# 10_12-Bit_RasPi-ADC_HAT_v21.net
KiCad netlist of a schematic drawn in EAGLE
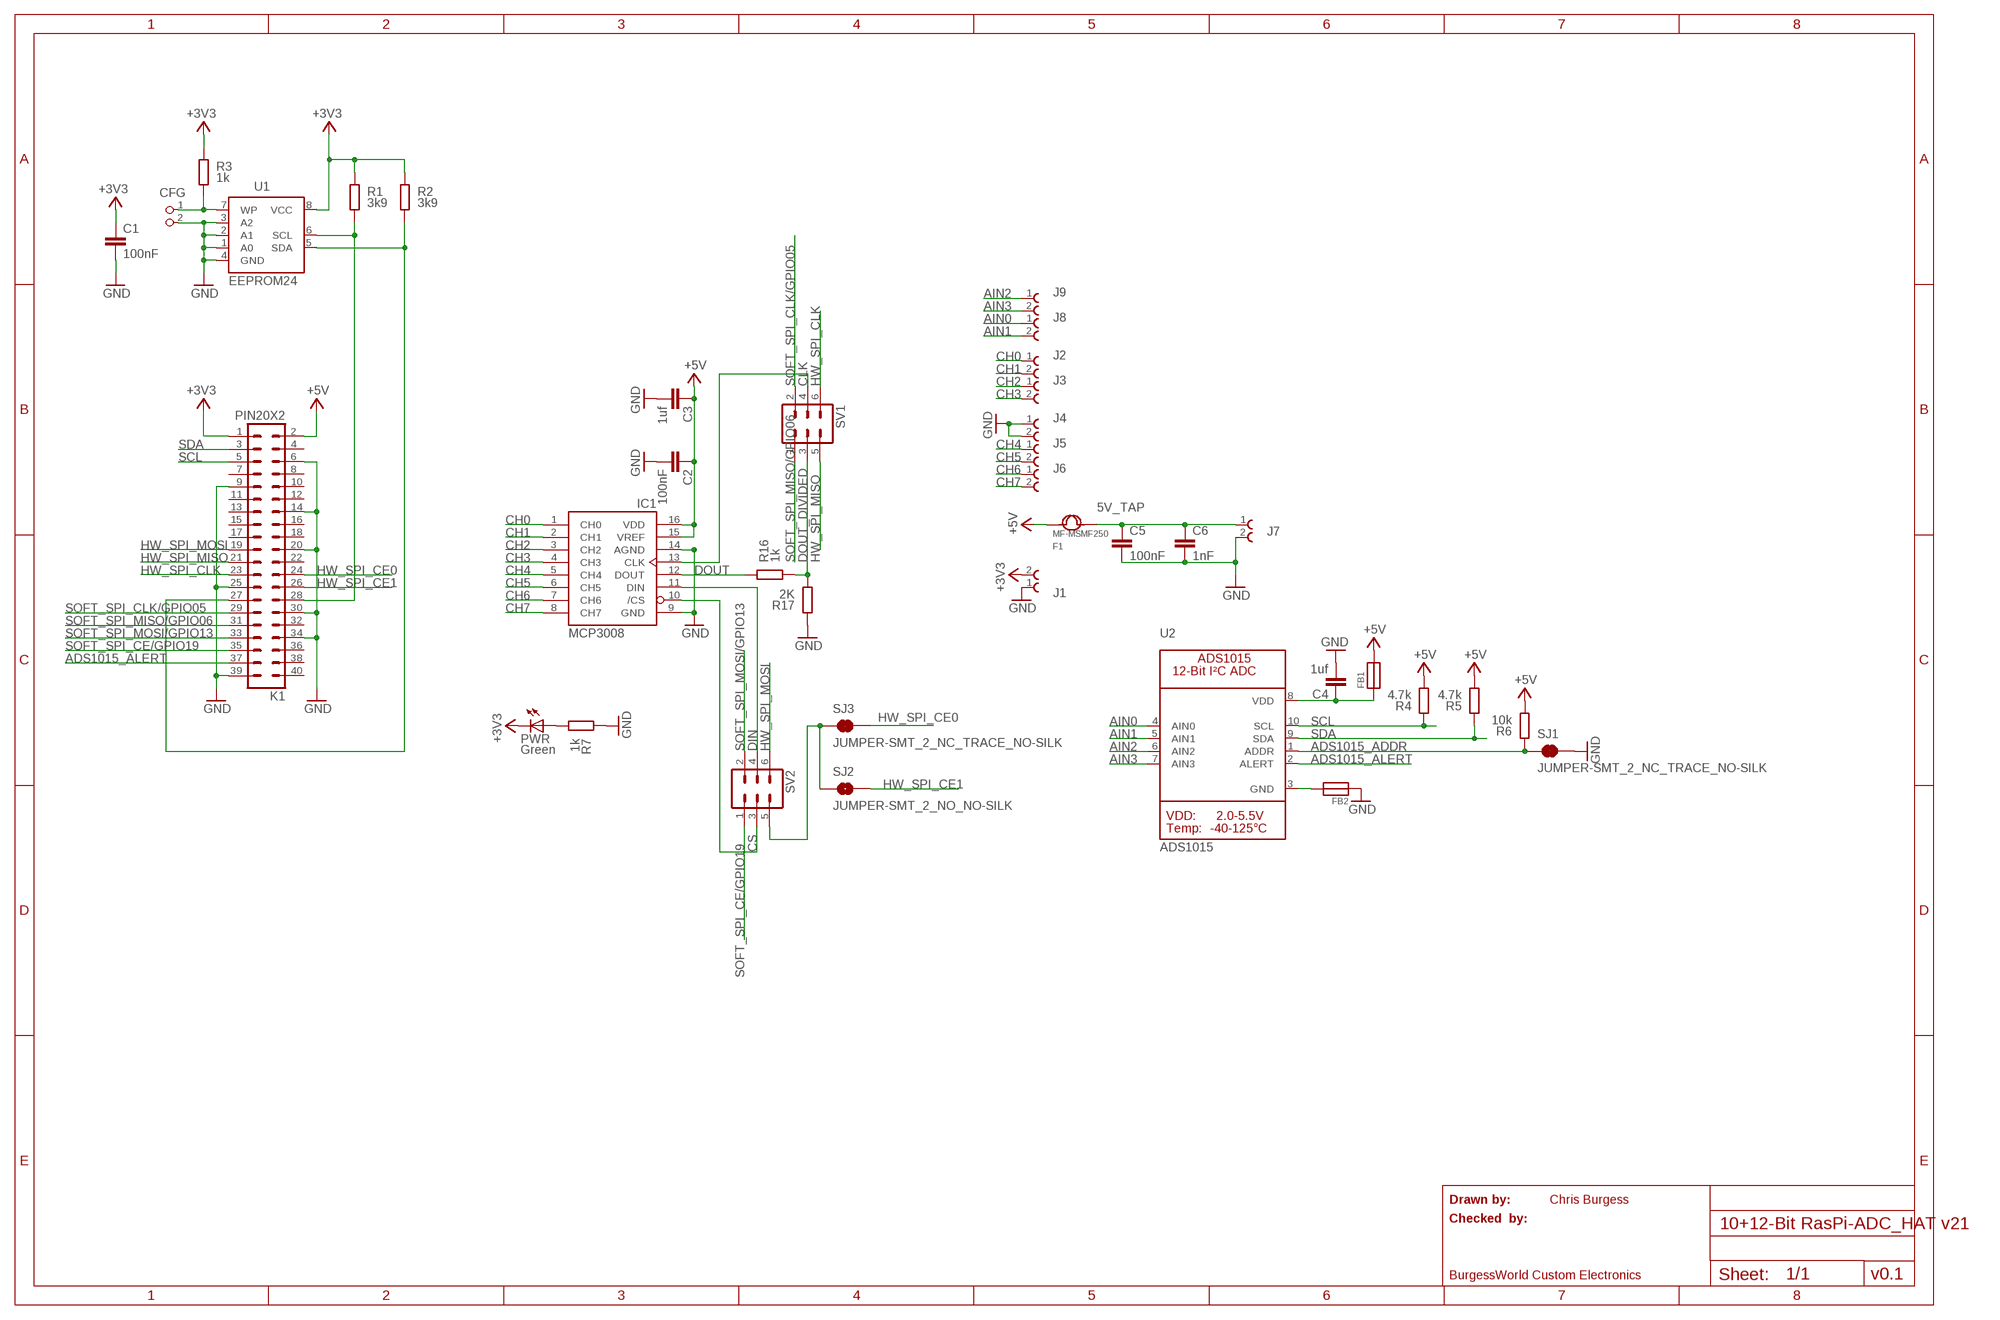
[diagram p0: schematic, sheet 1]

(export (version "E")
  (design (tool "Eeschema 10.0.6"))
  (components
    (comp (ref "C1")
      (value "100nF")
      (footprint "eagle-import:C0805K")
      (libsource (lib "eagle-import") (part "C-EUC0805K"))
    )
    (comp (ref "C2")
      (value "100nF")
      (footprint "eagle-import:C0805K")
      (libsource (lib "eagle-import") (part "C-EUC0805K"))
    )
    (comp (ref "C3")
      (value "1uf")
      (footprint "eagle-import:C0805K")
      (libsource (lib "eagle-import") (part "C-EUC0805K"))
    )
    (comp (ref "C4")
      (value "1uf")
      (footprint "eagle-import:C0805K")
      (libsource (lib "eagle-import") (part "C-EUC0805K"))
    )
    (comp (ref "C5")
      (value "100nF")
      (footprint "eagle-import:C0805K")
      (libsource (lib "eagle-import") (part "C-EUC0805K"))
    )
    (comp (ref "C6")
      (value "1nF")
      (footprint "eagle-import:C0805K")
      (libsource (lib "eagle-import") (part "C-EUC0805K"))
    )
    (comp (ref "CFG")
      (value "PIN2_100")
      (footprint "eagle-import:PIN_W_2")
      (libsource (lib "eagle-import") (part "PIN2_100"))
    )
    (comp (ref "F1")
      (value "MF-MSMF250")
      (footprint "eagle-import:F1812")
      (fields (field (name "MPN") "MF-MSMF050-2"))
      (libsource (lib "eagle-import") (part "SMD-PPTC-USE-PPTC-0.50A-15V-0.15OHM(1812)"))
    )
    (comp (ref "FB1")
      (value "FERRITE0805")
      (footprint "eagle-import:0805")
      (libsource (lib "eagle-import") (part "FERRITE0805"))
    )
    (comp (ref "FB2")
      (value "FERRITE0805")
      (footprint "eagle-import:0805")
      (libsource (lib "eagle-import") (part "FERRITE0805"))
    )
    (comp (ref "IC1")
      (value "MCP3008")
      (footprint "eagle-import:DIL16")
      (libsource (lib "eagle-import") (part "MCP3008"))
    )
    (comp (ref "J1")
      (value "691214110002")
      (footprint "eagle-import:691214110002")
      (libsource (lib "eagle-import") (part "691214110002"))
    )
    (comp (ref "J2")
      (value "691214110002")
      (footprint "eagle-import:691214110002")
      (libsource (lib "eagle-import") (part "691214110002"))
    )
    (comp (ref "J3")
      (value "691214110002")
      (footprint "eagle-import:691214110002")
      (libsource (lib "eagle-import") (part "691214110002"))
    )
    (comp (ref "J4")
      (value "691214110002")
      (footprint "eagle-import:691214110002")
      (libsource (lib "eagle-import") (part "691214110002"))
    )
    (comp (ref "J5")
      (value "691214110002")
      (footprint "eagle-import:691214110002")
      (libsource (lib "eagle-import") (part "691214110002"))
    )
    (comp (ref "J6")
      (value "691214110002")
      (footprint "eagle-import:691214110002")
      (libsource (lib "eagle-import") (part "691214110002"))
    )
    (comp (ref "J7")
      (value "691214110002")
      (footprint "eagle-import:691214110002")
      (libsource (lib "eagle-import") (part "691214110002"))
    )
    (comp (ref "J8")
      (value "691214110002")
      (footprint "eagle-import:691214110002")
      (libsource (lib "eagle-import") (part "691214110002"))
    )
    (comp (ref "J9")
      (value "691214110002")
      (footprint "eagle-import:691214110002")
      (libsource (lib "eagle-import") (part "691214110002"))
    )
    (comp (ref "K1")
      (value "PIN20X2")
      (footprint "eagle-import:PIN_20X2")
      (libsource (lib "eagle-import") (part "PIN20X2"))
    )
    (comp (ref "PWR")
      (value "Green")
      (footprint "eagle-import:CHIPLED_0805")
      (libsource (lib "eagle-import") (part "LEDCHIPLED_0805"))
    )
    (comp (ref "R1")
      (value "3k9")
      (footprint "eagle-import:M0805")
      (fields (field (name "TOLERANCE") "5%"))
      (libsource (lib "eagle-import") (part "R-EU_M0805"))
    )
    (comp (ref "R2")
      (value "3k9")
      (footprint "eagle-import:M0805")
      (fields (field (name "TOLERANCE") "5%"))
      (libsource (lib "eagle-import") (part "R-EU_M0805"))
    )
    (comp (ref "R3")
      (value "1k")
      (footprint "eagle-import:M0805")
      (fields (field (name "TOLERANCE") "5%"))
      (libsource (lib "eagle-import") (part "R-EU_M0805"))
    )
    (comp (ref "R4")
      (value "4.7k")
      (footprint "eagle-import:M0805")
      (fields (field (name "TOLERANCE") "5%"))
      (libsource (lib "eagle-import") (part "R-EU_M0805"))
    )
    (comp (ref "R5")
      (value "4.7k")
      (footprint "eagle-import:M0805")
      (fields (field (name "TOLERANCE") "5%"))
      (libsource (lib "eagle-import") (part "R-EU_M0805"))
    )
    (comp (ref "R6")
      (value "10k")
      (footprint "eagle-import:M0805")
      (fields (field (name "TOLERANCE") "5%"))
      (libsource (lib "eagle-import") (part "R-EU_M0805"))
    )
    (comp (ref "R7")
      (value "1k")
      (footprint "eagle-import:M0805")
      (fields (field (name "TOLERANCE") "5%"))
      (libsource (lib "eagle-import") (part "R-EU_M0805"))
    )
    (comp (ref "R16")
      (value "1k")
      (footprint "eagle-import:M0805")
      (fields (field (name "TOLERANCE") "5%"))
      (libsource (lib "eagle-import") (part "R-EU_M0805"))
    )
    (comp (ref "R17")
      (value "2K")
      (footprint "eagle-import:M0805")
      (fields (field (name "TOLERANCE") "5%"))
      (libsource (lib "eagle-import") (part "R-EU_M0805"))
    )
    (comp (ref "SJ1")
      (value "JUMPER-SMT_2_NC_TRACE_NO-SILK")
      (footprint "eagle-import:SMT-JUMPER_2_NC_TRACE_NO-SILK")
      (libsource (lib "eagle-import") (part "JUMPER-SMT_2_NC_TRACE_NO-SILK"))
    )
    (comp (ref "SJ2")
      (value "JUMPER-SMT_2_NO_NO-SILK")
      (footprint "eagle-import:SMT-JUMPER_2_NO_NO-SILK")
      (libsource (lib "eagle-import") (part "JUMPER-SMT_2_NO_NO-SILK"))
    )
    (comp (ref "SJ3")
      (value "JUMPER-SMT_2_NC_TRACE_NO-SILK")
      (footprint "eagle-import:SMT-JUMPER_2_NC_TRACE_NO-SILK")
      (libsource (lib "eagle-import") (part "JUMPER-SMT_2_NC_TRACE_NO-SILK"))
    )
    (comp (ref "SV1")
      (value "MA03-2")
      (footprint "eagle-import:MA03-2")
      (libsource (lib "eagle-import") (part "MA03-2"))
    )
    (comp (ref "SV2")
      (value "MA03-2")
      (footprint "eagle-import:MA03-2")
      (libsource (lib "eagle-import") (part "MA03-2"))
    )
    (comp (ref "U1")
      (value "EEPROM24")
      (footprint "eagle-import:SOIC8")
      (libsource (lib "eagle-import") (part "EEPROM24"))
    )
    (comp (ref "U2")
      (value "ADS1015")
      (footprint "eagle-import:MSOP10")
      (libsource (lib "eagle-import") (part "ADC_ADS1015"))
    )
  )
  (nets
    (net (code "1") (name "+3V3") (class "Default")
      (node (ref "C1") (pin "1") (pinfunction "1_1") (pintype "passive"))
      (node (ref "J1") (pin "2") (pinfunction "2_2") (pintype "passive"))
      (node (ref "K1") (pin "1") (pinfunction "1_1") (pintype "passive"))
      (node (ref "PWR") (pin "C") (pinfunction "C_C") (pintype "passive"))
      (node (ref "R1") (pin "2") (pinfunction "2_2") (pintype "passive"))
      (node (ref "R2") (pin "2") (pinfunction "2_2") (pintype "passive"))
      (node (ref "R3") (pin "2") (pinfunction "2_2") (pintype "passive"))
      (node (ref "U1") (pin "8") (pinfunction "VCC_8") (pintype "power_in"))
    )
    (net (code "2") (name "+5V") (class "Default")
      (node (ref "C2") (pin "1") (pinfunction "1_1") (pintype "passive"))
      (node (ref "C3") (pin "1") (pinfunction "1_1") (pintype "passive"))
      (node (ref "F1") (pin "1") (pinfunction "1_1") (pintype "bidirectional"))
      (node (ref "FB1") (pin "2") (pinfunction "P$2_2") (pintype "bidirectional"))
      (node (ref "IC1") (pin "15") (pinfunction "VREF_15") (pintype "input"))
      (node (ref "IC1") (pin "16") (pinfunction "VDD_16") (pintype "power_in"))
      (node (ref "K1") (pin "2") (pinfunction "2_2") (pintype "passive"))
      (node (ref "R4") (pin "1") (pinfunction "1_1") (pintype "passive"))
      (node (ref "R5") (pin "1") (pinfunction "1_1") (pintype "passive"))
      (node (ref "R6") (pin "1") (pinfunction "1_1") (pintype "passive"))
    )
    (net (code "3") (name "/5V_TAP") (class "Default")
      (node (ref "C5") (pin "1") (pinfunction "1_1") (pintype "passive"))
      (node (ref "C6") (pin "1") (pinfunction "1_1") (pintype "passive"))
      (node (ref "F1") (pin "2") (pinfunction "2_2") (pintype "bidirectional"))
      (node (ref "J7") (pin "1") (pinfunction "1_1") (pintype "passive"))
    )
    (net (code "4") (name "/ADS1015_ADDR") (class "Default")
      (node (ref "R6") (pin "2") (pinfunction "2_2") (pintype "passive"))
      (node (ref "SJ1") (pin "1") (pinfunction "1_1") (pintype "passive"))
      (node (ref "U2") (pin "1") (pinfunction "ADDR_1") (pintype "bidirectional"))
    )
    (net (code "5") (name "/ADS1015_ALERT") (class "Default")
      (node (ref "K1") (pin "37") (pinfunction "37_37") (pintype "passive"))
      (node (ref "U2") (pin "2") (pinfunction "ALERT_2") (pintype "bidirectional"))
    )
    (net (code "6") (name "/AIN0") (class "Default")
      (node (ref "J8") (pin "1") (pinfunction "1_1") (pintype "passive"))
      (node (ref "U2") (pin "4") (pinfunction "AIN0_4") (pintype "bidirectional"))
    )
    (net (code "7") (name "/AIN1") (class "Default")
      (node (ref "J8") (pin "2") (pinfunction "2_2") (pintype "passive"))
      (node (ref "U2") (pin "5") (pinfunction "AIN1_5") (pintype "bidirectional"))
    )
    (net (code "8") (name "/AIN2") (class "Default")
      (node (ref "J9") (pin "1") (pinfunction "1_1") (pintype "passive"))
      (node (ref "U2") (pin "6") (pinfunction "AIN2_6") (pintype "bidirectional"))
    )
    (net (code "9") (name "/AIN3") (class "Default")
      (node (ref "J9") (pin "2") (pinfunction "2_2") (pintype "passive"))
      (node (ref "U2") (pin "7") (pinfunction "AIN3_7") (pintype "bidirectional"))
    )
    (net (code "10") (name "/CH0") (class "Default")
      (node (ref "IC1") (pin "1") (pinfunction "CH0_1") (pintype "input"))
      (node (ref "J2") (pin "1") (pinfunction "1_1") (pintype "passive"))
    )
    (net (code "11") (name "/CH1") (class "Default")
      (node (ref "IC1") (pin "2") (pinfunction "CH1_2") (pintype "input"))
      (node (ref "J2") (pin "2") (pinfunction "2_2") (pintype "passive"))
    )
    (net (code "12") (name "/CH2") (class "Default")
      (node (ref "IC1") (pin "3") (pinfunction "CH2_3") (pintype "input"))
      (node (ref "J3") (pin "1") (pinfunction "1_1") (pintype "passive"))
    )
    (net (code "13") (name "/CH3") (class "Default")
      (node (ref "IC1") (pin "4") (pinfunction "CH3_4") (pintype "input"))
      (node (ref "J3") (pin "2") (pinfunction "2_2") (pintype "passive"))
    )
    (net (code "14") (name "/CH4") (class "Default")
      (node (ref "IC1") (pin "5") (pinfunction "CH4_5") (pintype "input"))
      (node (ref "J5") (pin "1") (pinfunction "1_1") (pintype "passive"))
    )
    (net (code "15") (name "/CH5") (class "Default")
      (node (ref "IC1") (pin "6") (pinfunction "CH5_6") (pintype "input"))
      (node (ref "J5") (pin "2") (pinfunction "2_2") (pintype "passive"))
    )
    (net (code "16") (name "/CH6") (class "Default")
      (node (ref "IC1") (pin "7") (pinfunction "CH6_7") (pintype "input"))
      (node (ref "J6") (pin "1") (pinfunction "1_1") (pintype "passive"))
    )
    (net (code "17") (name "/CH7") (class "Default")
      (node (ref "IC1") (pin "8") (pinfunction "CH7_8") (pintype "input"))
      (node (ref "J6") (pin "2") (pinfunction "2_2") (pintype "passive"))
    )
    (net (code "18") (name "/CLK") (class "Default")
      (node (ref "IC1") (pin "13") (pinfunction "CLK_13") (pintype "input"))
      (node (ref "SV1") (pin "4") (pinfunction "4_4") (pintype "passive"))
    )
    (net (code "19") (name "/CS") (class "Default")
      (node (ref "IC1") (pin "10") (pinfunction "/CS_10") (pintype "input"))
      (node (ref "SV2") (pin "3") (pinfunction "3_3") (pintype "passive"))
    )
    (net (code "20") (name "/DIN") (class "Default")
      (node (ref "IC1") (pin "11") (pinfunction "DIN_11") (pintype "input"))
      (node (ref "SV2") (pin "4") (pinfunction "4_4") (pintype "passive"))
    )
    (net (code "21") (name "/DOUT") (class "Default")
      (node (ref "IC1") (pin "12") (pinfunction "DOUT_12") (pintype "output"))
      (node (ref "R16") (pin "2") (pinfunction "2_2") (pintype "passive"))
    )
    (net (code "22") (name "/DOUT_DIVIDED") (class "Default")
      (node (ref "R16") (pin "1") (pinfunction "1_1") (pintype "passive"))
      (node (ref "R17") (pin "1") (pinfunction "1_1") (pintype "passive"))
      (node (ref "SV1") (pin "3") (pinfunction "3_3") (pintype "passive"))
    )
    (net (code "23") (name "/HW_SPI_CE0") (class "Default")
      (node (ref "K1") (pin "24") (pinfunction "24_24") (pintype "passive"))
      (node (ref "SJ3") (pin "2") (pinfunction "2_2") (pintype "passive"))
    )
    (net (code "24") (name "/HW_SPI_CE1") (class "Default")
      (node (ref "K1") (pin "26") (pinfunction "26_26") (pintype "passive"))
      (node (ref "SJ2") (pin "2") (pinfunction "2_2") (pintype "passive"))
    )
    (net (code "25") (name "/HW_SPI_CLK") (class "Default")
      (node (ref "K1") (pin "23") (pinfunction "23_23") (pintype "passive"))
      (node (ref "SV1") (pin "6") (pinfunction "6_6") (pintype "passive"))
    )
    (net (code "26") (name "/HW_SPI_MISO") (class "Default")
      (node (ref "K1") (pin "21") (pinfunction "21_21") (pintype "passive"))
      (node (ref "SV1") (pin "5") (pinfunction "5_5") (pintype "passive"))
    )
    (net (code "27") (name "/HW_SPI_MOSI") (class "Default")
      (node (ref "K1") (pin "19") (pinfunction "19_19") (pintype "passive"))
      (node (ref "SV2") (pin "6") (pinfunction "6_6") (pintype "passive"))
    )
    (net (code "28") (name "/SCL") (class "Default")
      (node (ref "K1") (pin "5") (pinfunction "5_5") (pintype "passive"))
      (node (ref "R4") (pin "2") (pinfunction "2_2") (pintype "passive"))
      (node (ref "U2") (pin "10") (pinfunction "SCL_10") (pintype "bidirectional"))
    )
    (net (code "29") (name "/SDA") (class "Default")
      (node (ref "K1") (pin "3") (pinfunction "3_3") (pintype "passive"))
      (node (ref "R5") (pin "2") (pinfunction "2_2") (pintype "passive"))
      (node (ref "U2") (pin "9") (pinfunction "SDA_9") (pintype "bidirectional"))
    )
    (net (code "30") (name "/SOFT_SPI_CE{slash}GPIO19") (class "Default")
      (node (ref "K1") (pin "35") (pinfunction "35_35") (pintype "passive"))
      (node (ref "SV2") (pin "1") (pinfunction "1_1") (pintype "passive"))
    )
    (net (code "31") (name "/SOFT_SPI_CLK{slash}GPIO05") (class "Default")
      (node (ref "K1") (pin "29") (pinfunction "29_29") (pintype "passive"))
      (node (ref "SV1") (pin "2") (pinfunction "2_2") (pintype "passive"))
    )
    (net (code "32") (name "/SOFT_SPI_MISO{slash}GPIO06") (class "Default")
      (node (ref "K1") (pin "31") (pinfunction "31_31") (pintype "passive"))
      (node (ref "SV1") (pin "1") (pinfunction "1_1") (pintype "passive"))
    )
    (net (code "33") (name "/SOFT_SPI_MOSI{slash}GPIO13") (class "Default")
      (node (ref "K1") (pin "33") (pinfunction "33_33") (pintype "passive"))
      (node (ref "SV2") (pin "2") (pinfunction "2_2") (pintype "passive"))
    )
    (net (code "34") (name "GND") (class "Default")
      (node (ref "C1") (pin "2") (pinfunction "2_2") (pintype "passive"))
      (node (ref "C2") (pin "2") (pinfunction "2_2") (pintype "passive"))
      (node (ref "C3") (pin "2") (pinfunction "2_2") (pintype "passive"))
      (node (ref "C4") (pin "2") (pinfunction "2_2") (pintype "passive"))
      (node (ref "C5") (pin "2") (pinfunction "2_2") (pintype "passive"))
      (node (ref "C6") (pin "2") (pinfunction "2_2") (pintype "passive"))
      (node (ref "CFG") (pin "2") (pinfunction "2_2") (pintype "passive"))
      (node (ref "FB2") (pin "1") (pinfunction "P$1_1") (pintype "bidirectional"))
      (node (ref "IC1") (pin "14") (pinfunction "AGND_14") (pintype "power_in"))
      (node (ref "IC1") (pin "9") (pinfunction "GND_9") (pintype "power_in"))
      (node (ref "J1") (pin "1") (pinfunction "1_1") (pintype "passive"))
      (node (ref "J4") (pin "1") (pinfunction "1_1") (pintype "passive"))
      (node (ref "J4") (pin "2") (pinfunction "2_2") (pintype "passive"))
      (node (ref "J7") (pin "2") (pinfunction "2_2") (pintype "passive"))
      (node (ref "K1") (pin "14") (pinfunction "14_14") (pintype "passive"))
      (node (ref "K1") (pin "20") (pinfunction "20_20") (pintype "passive"))
      (node (ref "K1") (pin "25") (pinfunction "25_25") (pintype "passive"))
      (node (ref "K1") (pin "30") (pinfunction "30_30") (pintype "passive"))
      (node (ref "K1") (pin "34") (pinfunction "34_34") (pintype "passive"))
      (node (ref "K1") (pin "39") (pinfunction "39_39") (pintype "passive"))
      (node (ref "K1") (pin "6") (pinfunction "6_6") (pintype "passive"))
      (node (ref "K1") (pin "9") (pinfunction "9_9") (pintype "passive"))
      (node (ref "R17") (pin "2") (pinfunction "2_2") (pintype "passive"))
      (node (ref "R7") (pin "2") (pinfunction "2_2") (pintype "passive"))
      (node (ref "SJ1") (pin "2") (pinfunction "2_2") (pintype "passive"))
      (node (ref "U1") (pin "1") (pinfunction "A0_1") (pintype "input"))
      (node (ref "U1") (pin "2") (pinfunction "A1_2") (pintype "input"))
      (node (ref "U1") (pin "3") (pinfunction "A2_3") (pintype "input"))
      (node (ref "U1") (pin "4") (pinfunction "GND_4") (pintype "power_in"))
    )
    (net (code "35") (name "Net-(FB1-P$1)") (class "Default")
      (node (ref "C4") (pin "1") (pinfunction "1_1") (pintype "passive"))
      (node (ref "FB1") (pin "1") (pinfunction "P$1_1") (pintype "bidirectional"))
      (node (ref "U2") (pin "8") (pinfunction "VDD_8") (pintype "bidirectional"))
    )
    (net (code "36") (name "Net-(FB2-P$2)") (class "Default")
      (node (ref "FB2") (pin "2") (pinfunction "P$2_2") (pintype "bidirectional"))
      (node (ref "U2") (pin "3") (pinfunction "GND_3") (pintype "bidirectional"))
    )
    (net (code "37") (name "Net-(PWR-PadA)") (class "Default")
      (node (ref "PWR") (pin "A") (pinfunction "A_A") (pintype "passive"))
      (node (ref "R7") (pin "1") (pinfunction "1_1") (pintype "passive"))
    )
    (net (code "38") (name "Net-(SJ2-Pad1)") (class "Default")
      (node (ref "SJ2") (pin "1") (pinfunction "1_1") (pintype "passive"))
      (node (ref "SJ3") (pin "1") (pinfunction "1_1") (pintype "passive"))
      (node (ref "SV2") (pin "5") (pinfunction "5_5") (pintype "passive"))
    )
    (net (code "39") (name "Net-(U1-SCL)") (class "Default")
      (node (ref "K1") (pin "28") (pinfunction "28_28") (pintype "passive"))
      (node (ref "R1") (pin "1") (pinfunction "1_1") (pintype "passive"))
      (node (ref "U1") (pin "6") (pinfunction "SCL_6") (pintype "input"))
    )
    (net (code "40") (name "Net-(U1-SDA)") (class "Default")
      (node (ref "K1") (pin "27") (pinfunction "27_27") (pintype "passive"))
      (node (ref "R2") (pin "1") (pinfunction "1_1") (pintype "passive"))
      (node (ref "U1") (pin "5") (pinfunction "SDA_5") (pintype "bidirectional"))
    )
    (net (code "41") (name "Net-(U1-WP)") (class "Default")
      (node (ref "CFG") (pin "1") (pinfunction "1_1") (pintype "passive"))
      (node (ref "R3") (pin "1") (pinfunction "1_1") (pintype "passive"))
      (node (ref "U1") (pin "7") (pinfunction "WP_7") (pintype "input"))
    )
    (net (code "42") (name "unconnected-(K1-Pad4)") (class "Default")
      (node (ref "K1") (pin "4") (pinfunction "4_4") (pintype "passive"))
    )
    (net (code "43") (name "unconnected-(K1-Pad7)") (class "Default")
      (node (ref "K1") (pin "7") (pinfunction "7_7") (pintype "passive"))
    )
    (net (code "44") (name "unconnected-(K1-Pad8)") (class "Default")
      (node (ref "K1") (pin "8") (pinfunction "8_8") (pintype "passive"))
    )
    (net (code "45") (name "unconnected-(K1-Pad10)") (class "Default")
      (node (ref "K1") (pin "10") (pinfunction "10_10") (pintype "passive"))
    )
    (net (code "46") (name "unconnected-(K1-Pad11)") (class "Default")
      (node (ref "K1") (pin "11") (pinfunction "11_11") (pintype "passive"))
    )
    (net (code "47") (name "unconnected-(K1-Pad12)") (class "Default")
      (node (ref "K1") (pin "12") (pinfunction "12_12") (pintype "passive"))
    )
    (net (code "48") (name "unconnected-(K1-Pad13)") (class "Default")
      (node (ref "K1") (pin "13") (pinfunction "13_13") (pintype "passive"))
    )
    (net (code "49") (name "unconnected-(K1-Pad15)") (class "Default")
      (node (ref "K1") (pin "15") (pinfunction "15_15") (pintype "passive"))
    )
    (net (code "50") (name "unconnected-(K1-Pad16)") (class "Default")
      (node (ref "K1") (pin "16") (pinfunction "16_16") (pintype "passive"))
    )
    (net (code "51") (name "unconnected-(K1-Pad17)") (class "Default")
      (node (ref "K1") (pin "17") (pinfunction "17_17") (pintype "passive"))
    )
    (net (code "52") (name "unconnected-(K1-Pad18)") (class "Default")
      (node (ref "K1") (pin "18") (pinfunction "18_18") (pintype "passive"))
    )
    (net (code "53") (name "unconnected-(K1-Pad22)") (class "Default")
      (node (ref "K1") (pin "22") (pinfunction "22_22") (pintype "passive"))
    )
    (net (code "54") (name "unconnected-(K1-Pad32)") (class "Default")
      (node (ref "K1") (pin "32") (pinfunction "32_32") (pintype "passive"))
    )
    (net (code "55") (name "unconnected-(K1-Pad36)") (class "Default")
      (node (ref "K1") (pin "36") (pinfunction "36_36") (pintype "passive"))
    )
    (net (code "56") (name "unconnected-(K1-Pad38)") (class "Default")
      (node (ref "K1") (pin "38") (pinfunction "38_38") (pintype "passive"))
    )
    (net (code "57") (name "unconnected-(K1-Pad40)") (class "Default")
      (node (ref "K1") (pin "40") (pinfunction "40_40") (pintype "passive"))
    )
  )
)
